# CH32V20x_WUI_DEMO.net
KiCad netlist of a schematic drawn in Altium Designer
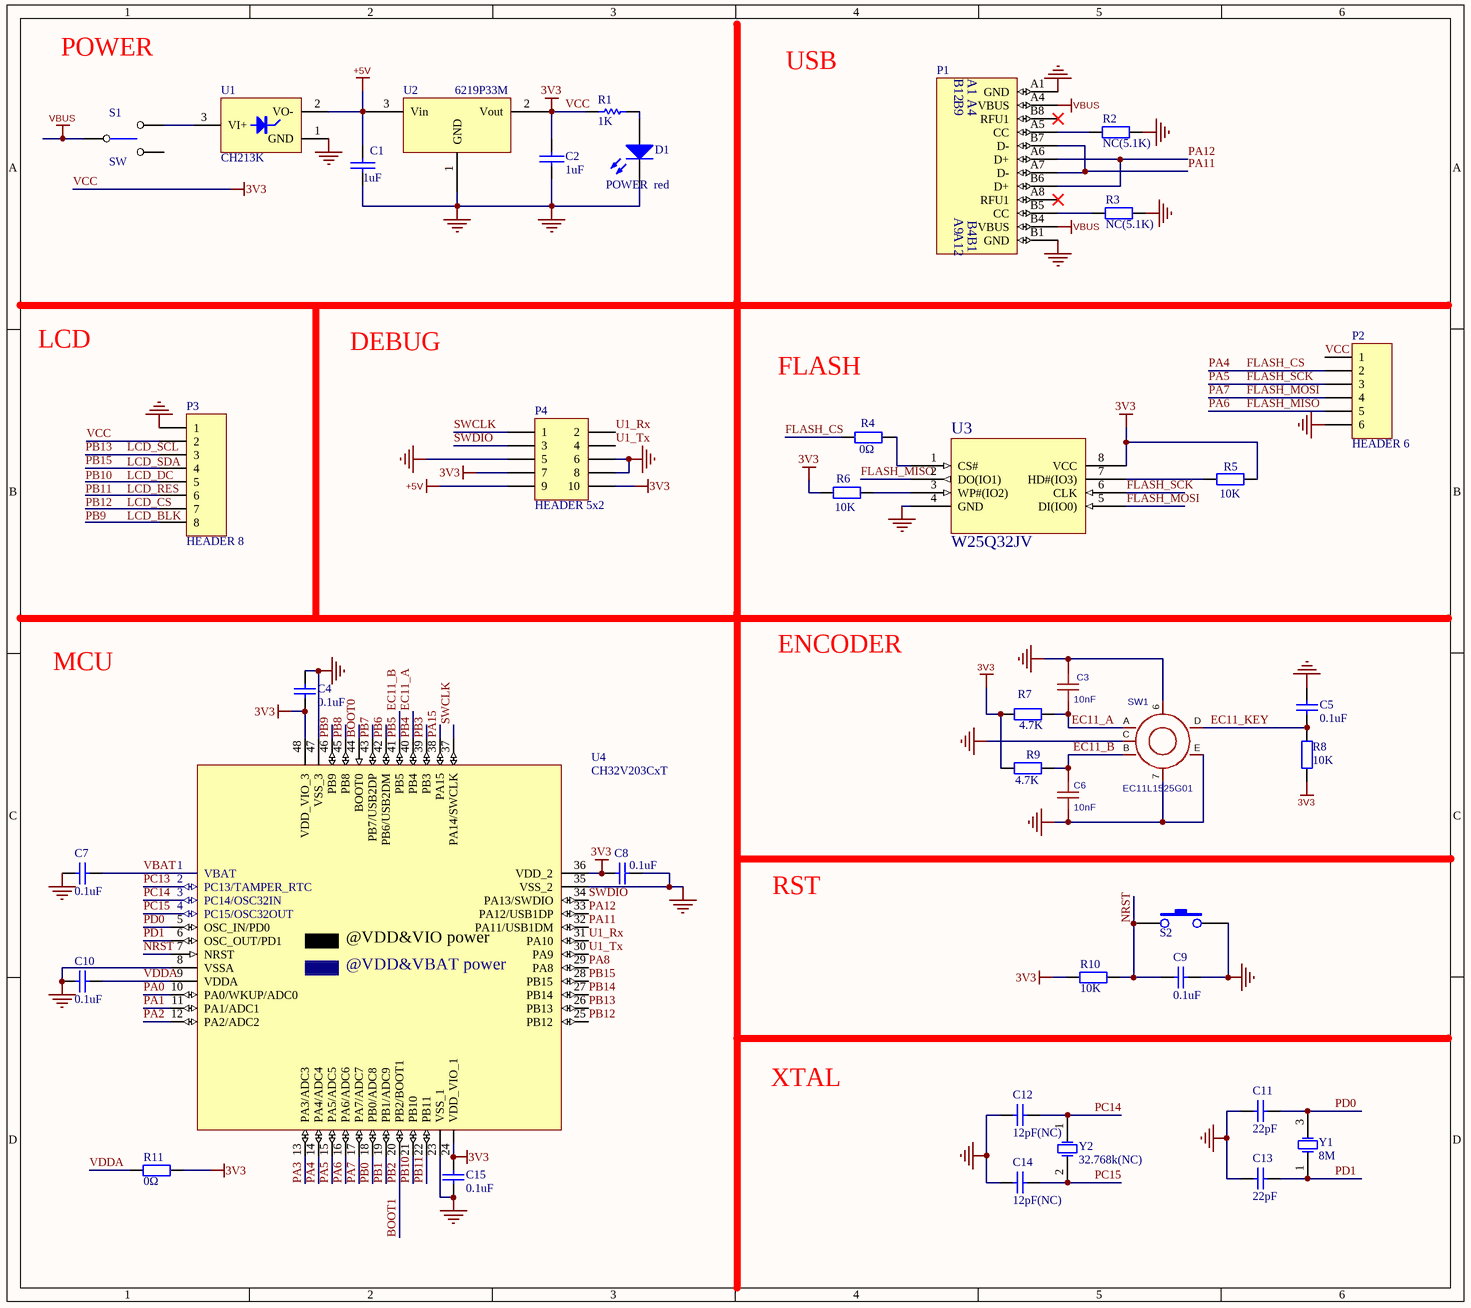
[diagram p0: CH32V20x_WUI_DEMO.schdoc]

(export (version "E")
  (design (tool "Eeschema 10.0.6"))
  (components
    (comp (ref "C1")
      (value "1uF")
      (footprint "0402_C")
      (description "Capacitor")
      (libsource (lib "*") (part "CAP"))
    )
    (comp (ref "C2")
      (value "1uF")
      (footprint "0402_C")
      (description "Capacitor")
      (libsource (lib "*") (part "CAP"))
    )
    (comp (ref "C3")
      (value "10nF")
      (footprint "0402_C")
      (libsource (lib "altium-import") (part "root_1_CAP_0603_"))
    )
    (comp (ref "C4")
      (value "0.1uF")
      (footprint "0402_C")
      (description "Capacitor")
      (fields (field (name "PUBLISHER") "Altium Limited"))
      (libsource (lib "*") (part "Cap"))
    )
    (comp (ref "C5")
      (value "0.1uF")
      (footprint "0402_C")
      (description "Capacitor")
      (fields (field (name "PUBLISHER") "Altium Limited"))
      (libsource (lib "*") (part "Cap"))
    )
    (comp (ref "C6")
      (value "10nF")
      (footprint "0402_C")
      (libsource (lib "altium-import") (part "root_3_CAP_0603_"))
    )
    (comp (ref "C7")
      (value "0.1uF")
      (footprint "0402_C")
      (description "Capacitor")
      (fields (field (name "PUBLISHER") "Altium Limited"))
      (libsource (lib "*") (part "Cap"))
    )
    (comp (ref "C8")
      (value "0.1uF")
      (footprint "0402_C")
      (description "Capacitor")
      (fields (field (name "PUBLISHER") "Altium Limited"))
      (libsource (lib "*") (part "Cap"))
    )
    (comp (ref "C9")
      (value "0.1uF")
      (footprint "0402_C")
      (description "Capacitor")
      (fields (field (name "PUBLISHER") "Altium Limited"))
      (libsource (lib "*") (part "Cap"))
    )
    (comp (ref "C10")
      (value "0.1uF")
      (footprint "0402_C")
      (description "Capacitor")
      (fields (field (name "PUBLISHER") "Altium Limited"))
      (libsource (lib "*") (part "Cap"))
    )
    (comp (ref "C11")
      (value "22pF")
      (footprint "0402_C")
      (description "Capacitor")
      (fields (field (name "PUBLISHER") "Altium Limited"))
      (libsource (lib "*") (part "Cap"))
    )
    (comp (ref "C12")
      (value "12pF(NC)")
      (footprint "0402_C")
      (description "Capacitor")
      (fields (field (name "PUBLISHER") "Altium Limited"))
      (libsource (lib "*") (part "Cap"))
    )
    (comp (ref "C13")
      (value "22pF")
      (footprint "0402_C")
      (description "Capacitor")
      (fields (field (name "PUBLISHER") "Altium Limited"))
      (libsource (lib "*") (part "Cap"))
    )
    (comp (ref "C14")
      (value "12pF(NC)")
      (footprint "0402_C")
      (description "Capacitor")
      (fields (field (name "PUBLISHER") "Altium Limited"))
      (libsource (lib "*") (part "Cap"))
    )
    (comp (ref "C15")
      (value "0.1uF")
      (footprint "0402_C")
      (description "Capacitor")
      (fields (field (name "PUBLISHER") "Altium Limited"))
      (libsource (lib "*") (part "Cap"))
    )
    (comp (ref "D1")
      (value "POWER  red")
      (footprint "0603+")
      (description "Typical INFRARED GaAs LED")
      (fields (field (name "PUBLISHER") "Altium Limited"))
      (libsource (lib "*") (part "LED0"))
    )
    (comp (ref "P1")
      (value "TYPE-C")
      (footprint "TYPE-C-Receptacle-2.0")
      (libsource (lib "*") (part "TYPE-C1"))
    )
    (comp (ref "P2")
      (value "HEADER 6")
      (footprint "SIP6-2.54mm")
      (description "Header, 6-Pin")
      (libsource (lib "wch_sch_others") (part "HEADER 6"))
    )
    (comp (ref "P3")
      (value "HEADER 8")
      (footprint "SIP8-2.54mm")
      (description "Header, 8-Pin")
      (libsource (lib "wch_sch_others") (part "HEADER 8"))
    )
    (comp (ref "P4")
      (value "HEADER 5x2")
      (footprint "MYPCB:IDC10-2.54mm")
      (description "Header, 5-Pin, Dual row")
      (libsource (lib "wch_sch_others") (part "HEADER 5x2"))
    )
    (comp (ref "R1")
      (value "1K")
      (footprint "0402")
      (description "Semiconductor Resistor")
      (fields (field (name "PUBLISHER") "Altium Limited"))
      (libsource (lib "*") (part "Res Semi"))
    )
    (comp (ref "R2")
      (value "NC(5.1K)")
      (footprint "0402")
      (description "Resistor")
      (libsource (lib "Miscellaneous Devices") (part "Res2"))
    )
    (comp (ref "R3")
      (value "NC(5.1K)")
      (footprint "0402")
      (description "Resistor")
      (libsource (lib "Miscellaneous Devices") (part "Res2"))
    )
    (comp (ref "R4")
      (value "0Ω")
      (footprint "0402")
      (description "Resistor")
      (fields (field (name "PUBLISHER") "Altium Limited"))
      (libsource (lib "*") (part "Res2"))
    )
    (comp (ref "R5")
      (value "10K")
      (footprint "0402")
      (description "Resistor")
      (fields (field (name "PUBLISHER") "Altium Limited"))
      (libsource (lib "*") (part "Res2"))
    )
    (comp (ref "R6")
      (value "10K")
      (footprint "0402")
      (description "Resistor")
      (fields (field (name "PUBLISHER") "Altium Limited"))
      (libsource (lib "*") (part "Res2"))
    )
    (comp (ref "R7")
      (value "4.7K")
      (footprint "0402")
      (description "Resistor")
      (fields (field (name "PUBLISHER") "Altium Limited"))
      (libsource (lib "*") (part "Res2"))
    )
    (comp (ref "R8")
      (value "10K")
      (footprint "0402")
      (description "Resistor")
      (fields (field (name "PUBLISHER") "Altium Limited"))
      (libsource (lib "") (part "Res2_2"))
    )
    (comp (ref "R9")
      (value "4.7K")
      (footprint "0402")
      (description "Resistor")
      (fields (field (name "PUBLISHER") "Altium Limited"))
      (libsource (lib "*") (part "Res2"))
    )
    (comp (ref "R10")
      (value "10K")
      (footprint "0402")
      (description "Resistor")
      (fields (field (name "PUBLISHER") "Altium Limited"))
      (libsource (lib "") (part "Res2_1"))
    )
    (comp (ref "R11")
      (value "0Ω")
      (footprint "0402")
      (description "Resistor")
      (fields (field (name "PUBLISHER") "Altium Limited"))
      (libsource (lib "") (part "Res2_1"))
    )
    (comp (ref "S1") (value "SW") (footprint "SW1") (libsource (lib "*") (part "SW")))
    (comp (ref "S2") (value "KEY") (footprint "贴片按键") (libsource (lib "*") (part "KEY")))
    (comp (ref "SW1")
      (value "EC11L1525G01")
      (footprint "SW-TH_ALPS_EC11L1525G01")
      (fields (field (name "MANUFACTURER") "ALPSALPINE(阿尔卑斯阿尔派)"))
      (libsource (lib "altium-import") (part "root_3_EC11L1525G01_"))
    )
    (comp (ref "U1")
      (value "CH213K")
      (footprint "SOT-23-3")
      (description "Ideal Diode 5V*1A")
      (libsource (lib "CHXXX") (part "CH213K"))
    )
    (comp (ref "U2")
      (value "6219P33M")
      (footprint "SOT-23")
      (libsource (lib "wch_sch_others") (part "6219P33M"))
    )
    (comp (ref "U3")
      (value "W25Q32JV")
      (footprint "SOIC-8_208mil")
      (libsource (lib "wch_sch_others") (part "W25Q32JV"))
    )
    (comp (ref "U4")
      (value "CH32V203CxT")
      (footprint "LQFP48")
      (description "RISC-V LMD-MCU, 144MHz, 2*USB FS, CAN")
      (libsource (lib "CHXXX") (part "CH32V203CxT"))
    )
    (comp (ref "Y1")
      (value "8M")
      (footprint "XT3225")
      (description "Crystal Oscillator")
      (fields (field (name "PUBLISHER") "Altium Limited"))
      (libsource (lib "*") (part "XTAL"))
    )
    (comp (ref "Y2")
      (value "32.768k(NC)")
      (footprint "FC-135")
      (description "Crystal Oscillator")
      (fields (field (name "PUBLISHER") "Altium Limited"))
      (libsource (lib "") (part "XTAL_1"))
    )
  )
  (nets
    (net (code "1") (name "+5V") (class "Default")
      (node (ref "C1") (pin "1") (pinfunction "1_1") (pintype "passive"))
      (node (ref "P4") (pin "9") (pinfunction "9_9") (pintype "passive"))
      (node (ref "U1") (pin "2") (pinfunction "VO-_2") (pintype "power_in"))
      (node (ref "U2") (pin "3") (pinfunction "Vin_3") (pintype "passive"))
    )
    (net (code "2") (name "/BOOT0") (class "Default")
      (node (ref "U4") (pin "44") (pinfunction "BOOT0_44") (pintype "input"))
    )
    (net (code "3") (name "/BOOT1") (class "Default")
      (node (ref "U4") (pin "20") (pinfunction "PB2/BOOT1_20") (pintype "bidirectional"))
    )
    (net (code "4") (name "/EC11_A") (class "Default")
      (node (ref "C3") (pin "1") (pinfunction "1_1") (pintype "passive"))
      (node (ref "R7") (pin "2") (pinfunction "2_2") (pintype "passive"))
      (node (ref "SW1") (pin "A") (pinfunction "A_A") (pintype "passive"))
      (node (ref "U4") (pin "40") (pinfunction "PB4_40") (pintype "bidirectional"))
    )
    (net (code "5") (name "/EC11_B") (class "Default")
      (node (ref "C6") (pin "1") (pinfunction "1_1") (pintype "passive"))
      (node (ref "R9") (pin "2") (pinfunction "2_2") (pintype "passive"))
      (node (ref "SW1") (pin "B") (pinfunction "B_B") (pintype "passive"))
      (node (ref "U4") (pin "41") (pinfunction "PB5_41") (pintype "bidirectional"))
    )
    (net (code "6") (name "/EC11_KEY") (class "Default")
      (node (ref "C5") (pin "2") (pinfunction "2_2") (pintype "passive"))
      (node (ref "R8") (pin "2") (pinfunction "2_2") (pintype "passive"))
      (node (ref "SW1") (pin "D") (pinfunction "D_D") (pintype "passive"))
    )
    (net (code "7") (name "/FLASH_CS") (class "Default")
      (node (ref "P2") (pin "2") (pinfunction "2_2") (pintype "passive"))
      (node (ref "R4") (pin "1") (pinfunction "1_1") (pintype "passive"))
      (node (ref "U4") (pin "14") (pinfunction "PA4/ADC4_14") (pintype "bidirectional"))
    )
    (net (code "8") (name "/FLASH_MISO") (class "Default")
      (node (ref "P2") (pin "5") (pinfunction "5_5") (pintype "passive"))
      (node (ref "U3") (pin "2") (pinfunction "DO(IO1)_2") (pintype "output"))
      (node (ref "U4") (pin "16") (pinfunction "PA6/ADC6_16") (pintype "bidirectional"))
    )
    (net (code "9") (name "/FLASH_MOSI") (class "Default")
      (node (ref "P2") (pin "4") (pinfunction "4_4") (pintype "passive"))
      (node (ref "U3") (pin "5") (pinfunction "DI(IO0)_5") (pintype "input"))
      (node (ref "U4") (pin "17") (pinfunction "PA7/ADC7_17") (pintype "bidirectional"))
    )
    (net (code "10") (name "/FLASH_SCK") (class "Default")
      (node (ref "P2") (pin "3") (pinfunction "3_3") (pintype "passive"))
      (node (ref "U3") (pin "6") (pinfunction "CLK_6") (pintype "input"))
      (node (ref "U4") (pin "15") (pinfunction "PA5/ADC5_15") (pintype "bidirectional"))
    )
    (net (code "15") (name "/LCD_SCL") (class "Default")
      (node (ref "P3") (pin "3") (pinfunction "3_3") (pintype "passive"))
      (node (ref "U4") (pin "26") (pinfunction "PB13_26") (pintype "bidirectional"))
    )
    (net (code "17") (name "/NRST") (class "Default")
      (node (ref "C9") (pin "2") (pinfunction "2_2") (pintype "passive"))
      (node (ref "R10") (pin "1") (pinfunction "1_1") (pintype "passive"))
      (node (ref "S2") (pin "1") (pinfunction "1_1") (pintype "passive"))
      (node (ref "U4") (pin "7") (pinfunction "NRST_7") (pintype "input"))
    )
    (net (code "18") (name "/PA0") (class "Default")
      (node (ref "U4") (pin "10") (pinfunction "PA0/WKUP/ADC0_10") (pintype "bidirectional"))
    )
    (net (code "19") (name "/PA1") (class "Default")
      (node (ref "U4") (pin "11") (pinfunction "PA1/ADC1_11") (pintype "bidirectional"))
    )
    (net (code "20") (name "/PA2") (class "Default")
      (node (ref "U4") (pin "12") (pinfunction "PA2/ADC2_12") (pintype "bidirectional"))
    )
    (net (code "21") (name "/PA3") (class "Default")
      (node (ref "U4") (pin "13") (pinfunction "PA3/ADC3_13") (pintype "bidirectional"))
    )
    (net (code "22") (name "/PA8") (class "Default")
      (node (ref "U4") (pin "29") (pinfunction "PA8_29") (pintype "bidirectional"))
    )
    (net (code "23") (name "/PA11") (class "Default")
      (node (ref "P1") (pin "A7") (pinfunction "D-_A7") (pintype "bidirectional"))
      (node (ref "P1") (pin "B7") (pinfunction "D-_B7") (pintype "bidirectional"))
      (node (ref "U4") (pin "32") (pinfunction "PA11/USB1DM_32") (pintype "bidirectional"))
    )
    (net (code "24") (name "/PA12") (class "Default")
      (node (ref "P1") (pin "A6") (pinfunction "D+_A6") (pintype "bidirectional"))
      (node (ref "P1") (pin "B6") (pinfunction "D+_B6") (pintype "bidirectional"))
      (node (ref "U4") (pin "33") (pinfunction "PA12/USB1DP_33") (pintype "bidirectional"))
    )
    (net (code "25") (name "/PA15") (class "Default")
      (node (ref "U4") (pin "38") (pinfunction "PA15_38") (pintype "bidirectional"))
    )
    (net (code "26") (name "/PB0") (class "Default")
      (node (ref "U4") (pin "18") (pinfunction "PB0/ADC8_18") (pintype "bidirectional"))
    )
    (net (code "27") (name "/PB1") (class "Default")
      (node (ref "U4") (pin "19") (pinfunction "PB1/ADC9_19") (pintype "bidirectional"))
    )
    (net (code "28") (name "/PB3") (class "Default")
      (node (ref "U4") (pin "39") (pinfunction "PB3_39") (pintype "bidirectional"))
    )
    (net (code "29") (name "/PB6") (class "Default")
      (node (ref "U4") (pin "42") (pinfunction "PB6/USB2DM_42") (pintype "bidirectional"))
    )
    (net (code "30") (name "/PB7") (class "Default")
      (node (ref "U4") (pin "43") (pinfunction "PB7/USB2DP_43") (pintype "bidirectional"))
    )
    (net (code "31") (name "/PB8") (class "Default")
      (node (ref "U4") (pin "45") (pinfunction "PB8_45") (pintype "bidirectional"))
    )
    (net (code "32") (name "/PB9") (class "Default")
      (node (ref "U4") (pin "46") (pinfunction "PB9_46") (pintype "bidirectional"))
    )
    (net (code "33") (name "/PB10") (class "Default")
      (node (ref "U4") (pin "21") (pinfunction "PB10_21") (pintype "bidirectional"))
    )
    (net (code "34") (name "/PB11") (class "Default")
      (node (ref "U4") (pin "22") (pinfunction "PB11_22") (pintype "bidirectional"))
    )
    (net (code "35") (name "/PB12") (class "Default")
      (node (ref "U4") (pin "25") (pinfunction "PB12_25") (pintype "bidirectional"))
    )
    (net (code "36") (name "/PB14") (class "Default")
      (node (ref "U4") (pin "27") (pinfunction "PB14_27") (pintype "bidirectional"))
    )
    (net (code "37") (name "/PB15") (class "Default")
      (node (ref "P3") (pin "4") (pinfunction "4_4") (pintype "passive"))
      (node (ref "U4") (pin "28") (pinfunction "PB15_28") (pintype "bidirectional"))
    )
    (net (code "38") (name "/PC13") (class "Default")
      (node (ref "U4") (pin "2") (pinfunction "PC13/TAMPER_RTC_2") (pintype "bidirectional"))
    )
    (net (code "39") (name "/PC14") (class "Default")
      (node (ref "C12") (pin "1") (pinfunction "1_1") (pintype "passive"))
      (node (ref "U4") (pin "3") (pinfunction "PC14/OSC32IN_3") (pintype "bidirectional"))
      (node (ref "Y2") (pin "1") (pinfunction "OSC1_1") (pintype "passive"))
    )
    (net (code "40") (name "/PC15") (class "Default")
      (node (ref "C14") (pin "1") (pinfunction "1_1") (pintype "passive"))
      (node (ref "U4") (pin "4") (pinfunction "PC15/OSC32OUT_4") (pintype "bidirectional"))
      (node (ref "Y2") (pin "2") (pinfunction "OSC2_2") (pintype "passive"))
    )
    (net (code "41") (name "/PD0") (class "Default")
      (node (ref "C11") (pin "2") (pinfunction "2_2") (pintype "passive"))
      (node (ref "U4") (pin "5") (pinfunction "OSC_IN/PD0_5") (pintype "bidirectional"))
      (node (ref "Y1") (pin "3") (pinfunction "OSC2_3") (pintype "passive"))
    )
    (net (code "42") (name "/PD1") (class "Default")
      (node (ref "C13") (pin "2") (pinfunction "2_2") (pintype "passive"))
      (node (ref "U4") (pin "6") (pinfunction "OSC_OUT/PD1_6") (pintype "bidirectional"))
      (node (ref "Y1") (pin "1") (pinfunction "OSC1_1") (pintype "passive"))
    )
    (net (code "43") (name "/SWCLK") (class "Default")
      (node (ref "P4") (pin "1") (pinfunction "1_1") (pintype "passive"))
      (node (ref "U4") (pin "37") (pinfunction "PA14/SWCLK_37") (pintype "bidirectional"))
    )
    (net (code "44") (name "/SWDIO") (class "Default")
      (node (ref "P4") (pin "3") (pinfunction "3_3") (pintype "passive"))
      (node (ref "U4") (pin "34") (pinfunction "PA13/SWDIO_34") (pintype "bidirectional"))
    )
    (net (code "45") (name "/U1_Rx") (class "Default")
      (node (ref "P4") (pin "2") (pinfunction "2_2") (pintype "passive"))
      (node (ref "U4") (pin "31") (pinfunction "PA10_31") (pintype "bidirectional"))
    )
    (net (code "46") (name "/U1_Tx") (class "Default")
      (node (ref "P4") (pin "4") (pinfunction "4_4") (pintype "passive"))
      (node (ref "U4") (pin "30") (pinfunction "PA9_30") (pintype "bidirectional"))
    )
    (net (code "47") (name "/VBAT") (class "Default")
      (node (ref "C7") (pin "1") (pinfunction "1_1") (pintype "passive"))
      (node (ref "U4") (pin "1") (pinfunction "VBAT_1") (pintype "power_in"))
    )
    (net (code "48") (name "/VDDA") (class "Default")
      (node (ref "C10") (pin "1") (pinfunction "1_1") (pintype "passive"))
      (node (ref "R11") (pin "2") (pinfunction "2_2") (pintype "passive"))
      (node (ref "U4") (pin "9") (pinfunction "VDDA_9") (pintype "power_in"))
    )
    (net (code "49") (name "3V3") (class "Default")
      (node (ref "C15") (pin "2") (pinfunction "2_2") (pintype "passive"))
      (node (ref "C2") (pin "1") (pinfunction "1_1") (pintype "passive"))
      (node (ref "C4") (pin "2") (pinfunction "2_2") (pintype "passive"))
      (node (ref "C8") (pin "2") (pinfunction "2_2") (pintype "passive"))
      (node (ref "P2") (pin "1") (pinfunction "1_1") (pintype "passive"))
      (node (ref "P3") (pin "2") (pinfunction "2_2") (pintype "passive"))
      (node (ref "P4") (pin "10") (pinfunction "10_10") (pintype "passive"))
      (node (ref "P4") (pin "7") (pinfunction "7_7") (pintype "passive"))
      (node (ref "R1") (pin "2") (pinfunction "2_2") (pintype "passive"))
      (node (ref "R10") (pin "2") (pinfunction "2_2") (pintype "passive"))
      (node (ref "R11") (pin "1") (pinfunction "1_1") (pintype "passive"))
      (node (ref "R5") (pin "2") (pinfunction "2_2") (pintype "passive"))
      (node (ref "R6") (pin "1") (pinfunction "1_1") (pintype "passive"))
      (node (ref "R7") (pin "1") (pinfunction "1_1") (pintype "passive"))
      (node (ref "R8") (pin "1") (pinfunction "1_1") (pintype "passive"))
      (node (ref "R9") (pin "1") (pinfunction "1_1") (pintype "passive"))
      (node (ref "U2") (pin "2") (pinfunction "Vout_2") (pintype "passive"))
      (node (ref "U3") (pin "8") (pinfunction "VCC_8") (pintype "power_in"))
      (node (ref "U4") (pin "24") (pinfunction "VDD_VIO_1_24") (pintype "power_in"))
      (node (ref "U4") (pin "36") (pinfunction "VDD_2_36") (pintype "power_in"))
      (node (ref "U4") (pin "48") (pinfunction "VDD_VIO_3_48") (pintype "power_in"))
    )
    (net (code "50") (name "GND") (class "Default")
      (node (ref "C1") (pin "2") (pinfunction "2_2") (pintype "passive"))
      (node (ref "C10") (pin "2") (pinfunction "2_2") (pintype "passive"))
      (node (ref "C11") (pin "1") (pinfunction "1_1") (pintype "passive"))
      (node (ref "C12") (pin "2") (pinfunction "2_2") (pintype "passive"))
      (node (ref "C13") (pin "1") (pinfunction "1_1") (pintype "passive"))
      (node (ref "C14") (pin "2") (pinfunction "2_2") (pintype "passive"))
      (node (ref "C15") (pin "1") (pinfunction "1_1") (pintype "passive"))
      (node (ref "C2") (pin "2") (pinfunction "2_2") (pintype "passive"))
      (node (ref "C3") (pin "2") (pinfunction "2_2") (pintype "passive"))
      (node (ref "C4") (pin "1") (pinfunction "1_1") (pintype "passive"))
      (node (ref "C5") (pin "1") (pinfunction "1_1") (pintype "passive"))
      (node (ref "C6") (pin "2") (pinfunction "2_2") (pintype "passive"))
      (node (ref "C7") (pin "2") (pinfunction "2_2") (pintype "passive"))
      (node (ref "C8") (pin "1") (pinfunction "1_1") (pintype "passive"))
      (node (ref "C9") (pin "1") (pinfunction "1_1") (pintype "passive"))
      (node (ref "D1") (pin "2") (pinfunction "K_2") (pintype "passive"))
      (node (ref "P1") (pin "A1") (pinfunction "GND_A1") (pintype "bidirectional"))
      (node (ref "P1") (pin "B1") (pinfunction "GND_B1") (pintype "bidirectional"))
      (node (ref "P2") (pin "6") (pinfunction "6_6") (pintype "passive"))
      (node (ref "P3") (pin "1") (pinfunction "1_1") (pintype "passive"))
      (node (ref "P4") (pin "5") (pinfunction "5_5") (pintype "passive"))
      (node (ref "P4") (pin "6") (pinfunction "6_6") (pintype "passive"))
      (node (ref "P4") (pin "8") (pinfunction "8_8") (pintype "passive"))
      (node (ref "R2") (pin "2") (pinfunction "2_2") (pintype "passive"))
      (node (ref "R3") (pin "2") (pinfunction "2_2") (pintype "passive"))
      (node (ref "S2") (pin "2") (pinfunction "2_2") (pintype "passive"))
      (node (ref "SW1") (pin "6") (pinfunction "EH_6") (pintype "passive"))
      (node (ref "SW1") (pin "7") (pinfunction "EH_7") (pintype "passive"))
      (node (ref "SW1") (pin "C") (pinfunction "C_C") (pintype "passive"))
      (node (ref "SW1") (pin "E") (pinfunction "E_E") (pintype "passive"))
      (node (ref "U1") (pin "1") (pinfunction "GND_1") (pintype "power_in"))
      (node (ref "U2") (pin "1") (pinfunction "GND_1") (pintype "passive"))
      (node (ref "U3") (pin "4") (pinfunction "GND_4") (pintype "power_in"))
      (node (ref "U4") (pin "23") (pinfunction "VSS_1_23") (pintype "power_in"))
      (node (ref "U4") (pin "35") (pinfunction "VSS_2_35") (pintype "power_in"))
      (node (ref "U4") (pin "47") (pinfunction "VSS_3_47") (pintype "power_in"))
      (node (ref "U4") (pin "8") (pinfunction "VSSA_8") (pintype "power_in"))
    )
    (net (code "51") (name "Net-(D1-A)") (class "Default")
      (node (ref "D1") (pin "1") (pinfunction "A_1") (pintype "passive"))
      (node (ref "R1") (pin "1") (pinfunction "1_1") (pintype "passive"))
    )
    (net (code "52") (name "Net-(P1-CC-PadA5)") (class "Default")
      (node (ref "P1") (pin "A5") (pinfunction "CC_A5") (pintype "bidirectional"))
      (node (ref "R2") (pin "1") (pinfunction "1_1") (pintype "passive"))
    )
    (net (code "53") (name "Net-(P1-CC-PadB5)") (class "Default")
      (node (ref "P1") (pin "B5") (pinfunction "CC_B5") (pintype "bidirectional"))
      (node (ref "R3") (pin "1") (pinfunction "1_1") (pintype "passive"))
    )
    (net (code "54") (name "Net-(U1-VI+)") (class "Default")
      (node (ref "S1") (pin "3") (pinfunction "3_3") (pintype "passive"))
      (node (ref "U1") (pin "3") (pinfunction "VI+_3") (pintype "power_in"))
    )
    (net (code "55") (name "Net-(U3-CS#)") (class "Default")
      (node (ref "R4") (pin "2") (pinfunction "2_2") (pintype "passive"))
      (node (ref "U3") (pin "1") (pinfunction "CS#_1") (pintype "input"))
    )
    (net (code "56") (name "Net-(U3-HD#(IO3))") (class "Default")
      (node (ref "R5") (pin "1") (pinfunction "1_1") (pintype "passive"))
      (node (ref "U3") (pin "7") (pinfunction "HD#(IO3)_7") (pintype "power_in"))
    )
    (net (code "57") (name "Net-(U3-WP#(IO2))") (class "Default")
      (node (ref "R6") (pin "2") (pinfunction "2_2") (pintype "passive"))
      (node (ref "U3") (pin "3") (pinfunction "WP#(IO2)_3") (pintype "input"))
    )
    (net (code "58") (name "VBUS") (class "Default")
      (node (ref "P1") (pin "A4") (pinfunction "VBUS_A4") (pintype "bidirectional"))
      (node (ref "P1") (pin "B4") (pinfunction "VBUS_B4") (pintype "bidirectional"))
      (node (ref "S1") (pin "1") (pinfunction "1_1") (pintype "passive"))
    )
    (net (code "59") (name "unconnected-(P1-RFU1-PadA8)") (class "Default")
      (node (ref "P1") (pin "A8") (pinfunction "RFU1_A8") (pintype "bidirectional+no_connect"))
    )
    (net (code "60") (name "unconnected-(P1-RFU1-PadB8)") (class "Default")
      (node (ref "P1") (pin "B8") (pinfunction "RFU1_B8") (pintype "bidirectional+no_connect"))
    )
    (net (code "61") (name "unconnected-(P3-Pad5)") (class "Default")
      (node (ref "P3") (pin "5") (pinfunction "5_5") (pintype "passive"))
    )
    (net (code "62") (name "unconnected-(P3-Pad6)") (class "Default")
      (node (ref "P3") (pin "6") (pinfunction "6_6") (pintype "passive"))
    )
    (net (code "63") (name "unconnected-(P3-Pad7)") (class "Default")
      (node (ref "P3") (pin "7") (pinfunction "7_7") (pintype "passive"))
    )
    (net (code "64") (name "unconnected-(P3-Pad8)") (class "Default")
      (node (ref "P3") (pin "8") (pinfunction "8_8") (pintype "passive"))
    )
    (net (code "65") (name "unconnected-(S1-Pad2)") (class "Default")
      (node (ref "S1") (pin "2") (pinfunction "2_2") (pintype "passive"))
    )
  )
)
